# Measurements.net
KiCad netlist of a schematic drawn in Altium Designer
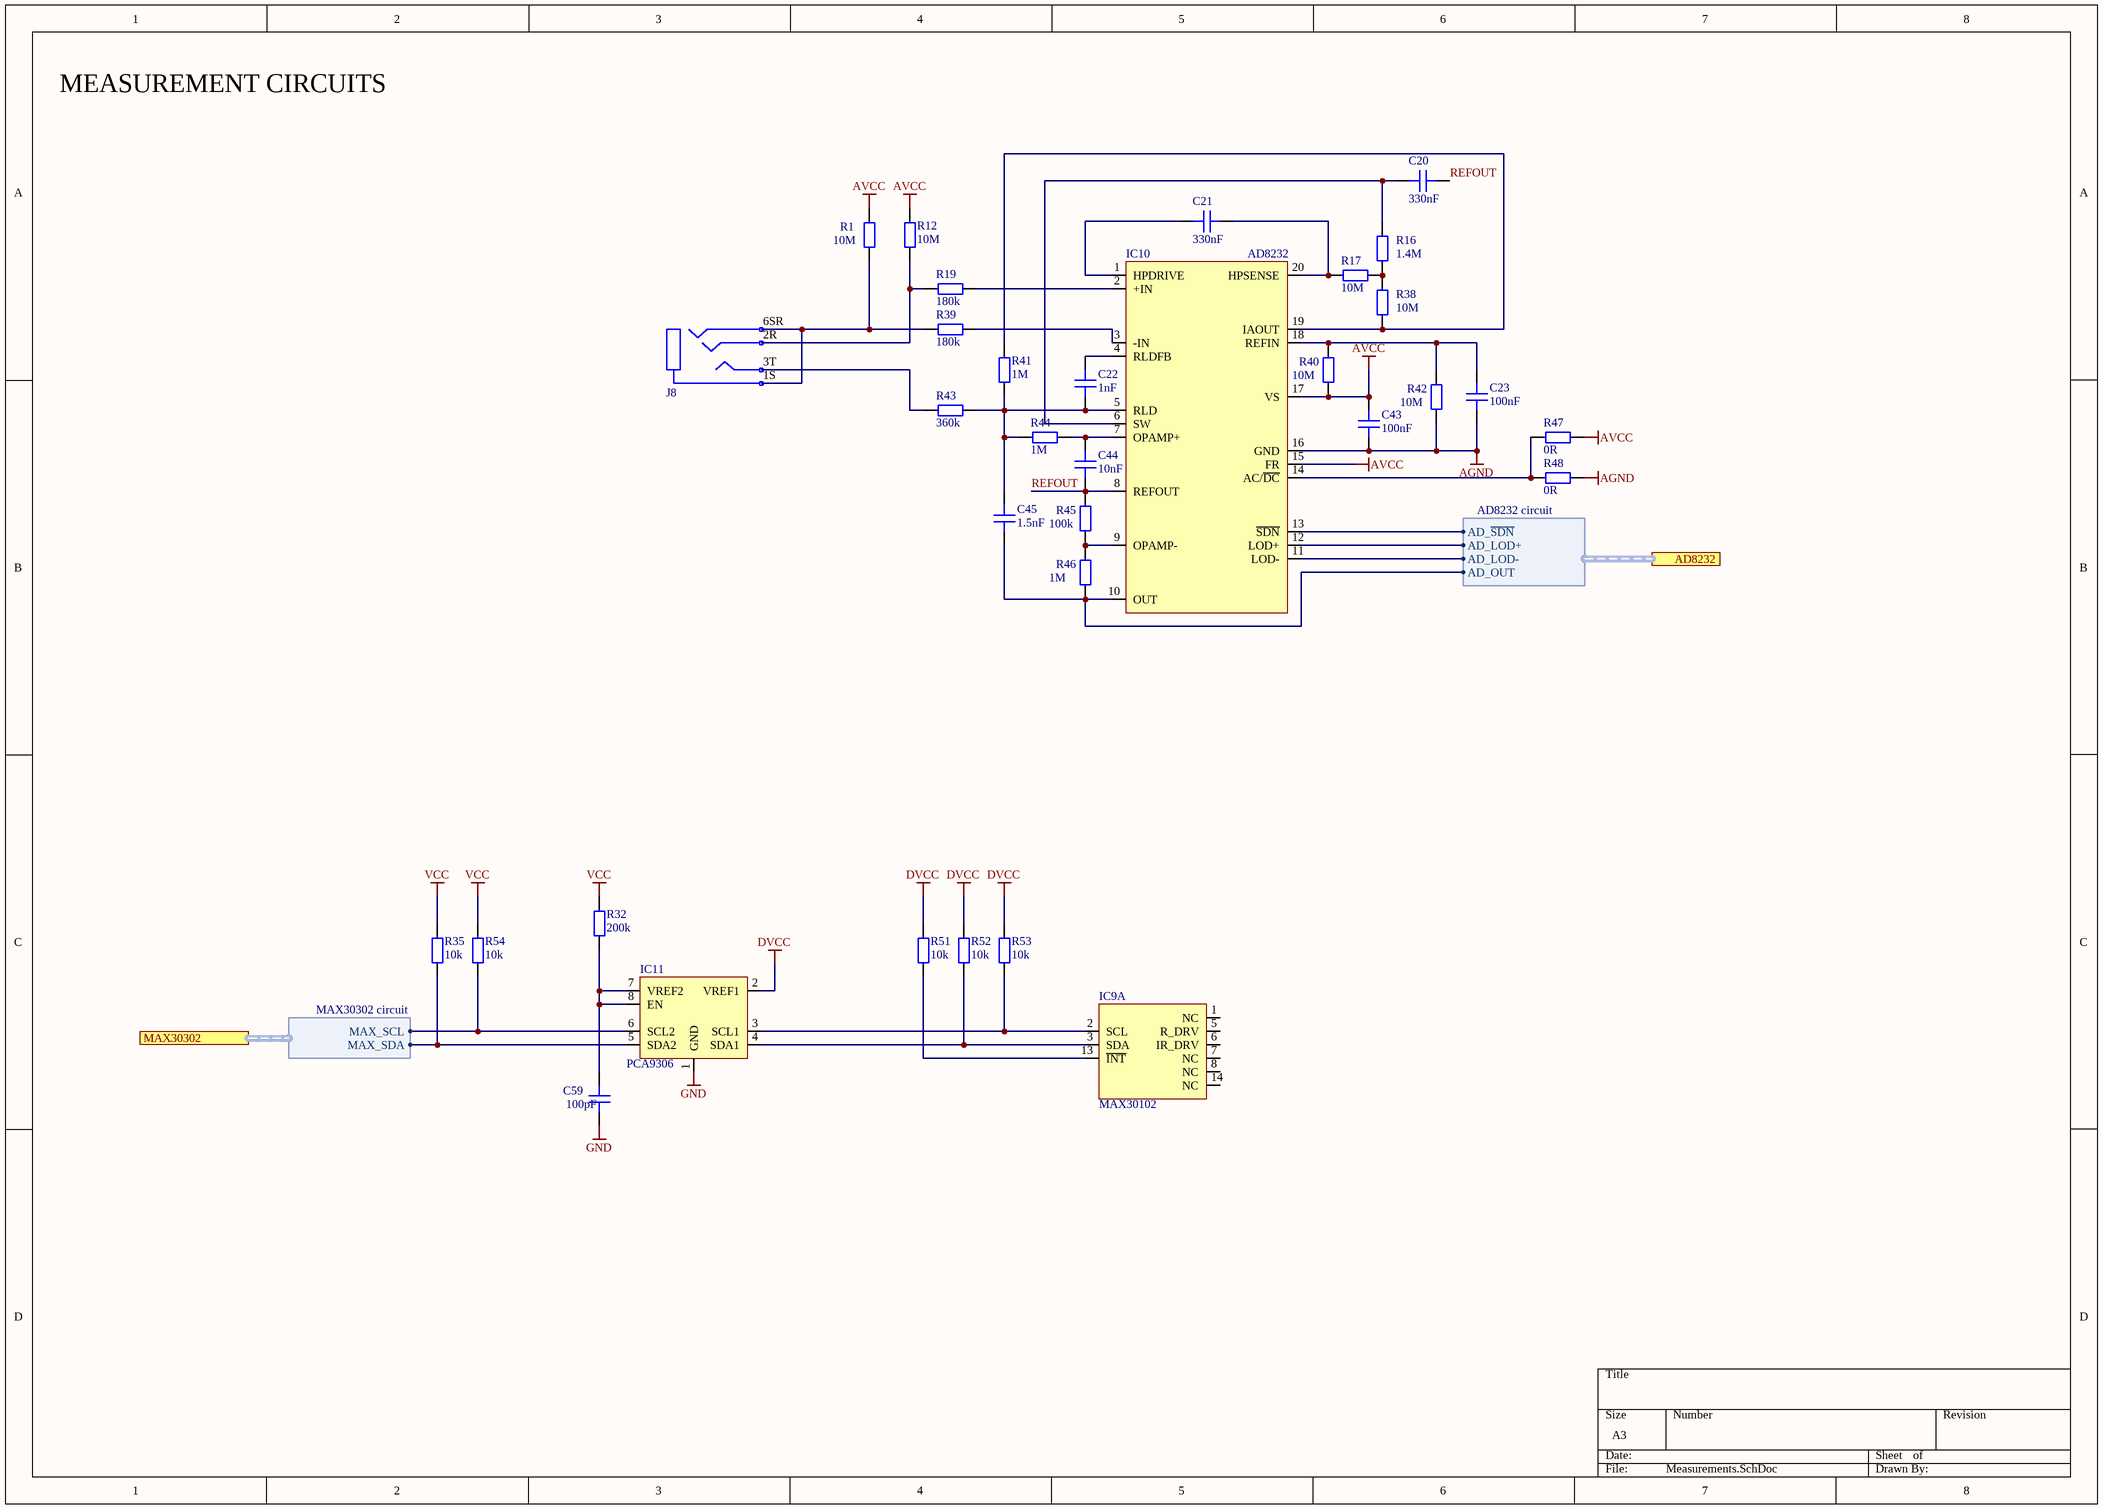
[diagram p0: Measurements.SchDoc]

(export (version "E")
  (design (tool "Eeschema 10.0.6"))
  (components
    (comp (ref "C20")
      (value "330nF")
      (footprint "CAP 0603")
      (description "SMT Capacitor")
      (libsource (lib "Passive") (part "Capacitor"))
    )
    (comp (ref "C21")
      (value "330nF")
      (footprint "CAP 0603")
      (description "SMT Capacitor")
      (libsource (lib "Passive") (part "Capacitor"))
    )
    (comp (ref "C22")
      (value "1nF")
      (footprint "CAP 0603")
      (description "SMT Capacitor")
      (libsource (lib "Passive") (part "Capacitor"))
    )
    (comp (ref "C23")
      (value "100nF")
      (footprint "CAP 0603")
      (description "SMT Capacitor")
      (libsource (lib "Passive") (part "Capacitor"))
    )
    (comp (ref "C43")
      (value "100nF")
      (footprint "CAP 0603")
      (description "SMT Capacitor")
      (libsource (lib "Passive") (part "Capacitor"))
    )
    (comp (ref "C44")
      (value "10nF")
      (footprint "CAP 0603")
      (description "SMT Capacitor")
      (libsource (lib "Passive") (part "Capacitor"))
    )
    (comp (ref "C45")
      (value "1.5nF")
      (footprint "CAP 0603")
      (description "SMT Capacitor")
      (libsource (lib "Passive") (part "Capacitor"))
    )
    (comp (ref "C59")
      (value "100pF")
      (footprint "CAP 0603")
      (description "SMT Capacitor")
      (libsource (lib "Passive") (part "Capacitor"))
    )
    (comp (ref "IC9")
      (value "MAX30102")
      (footprint "MAX30102")
      (description "Pulse Oximeter and Heart-Rate Sensor")
      (libsource (lib "IC") (part "MAX30102"))
    )
    (comp (ref "IC10")
      (value "AD8232")
      (footprint "LFCSP 20")
      (description "Single-Lead, Heart Rate Monitor Front End")
      (libsource (lib "IC") (part "AD8232"))
    )
    (comp (ref "IC11")
      (value "PCA9306")
      (footprint "SSOP8")
      (description "Dual Bidirectional I2C Bus and SMBus Voltage-Level Translator")
      (libsource (lib "IC") (part "PCA9306"))
    )
    (comp (ref "J8")
      (value "4 pin")
      (footprint "CLIFF FC68126")
      (description "Jack 3,5mm, dock, female")
      (libsource (lib "Connectors") (part "CLIFF FC68127 3.5mm"))
    )
    (comp (ref "R1")
      (value "10M")
      (footprint "RES 0603")
      (description "SMDResistor")
      (libsource (lib "Passive") (part "Resistor"))
    )
    (comp (ref "R12")
      (value "10M")
      (footprint "RES 0603")
      (description "SMDResistor")
      (libsource (lib "Passive") (part "Resistor"))
    )
    (comp (ref "R16")
      (value "1.4M")
      (footprint "RES 0603")
      (description "SMDResistor")
      (libsource (lib "Passive") (part "Resistor"))
    )
    (comp (ref "R17")
      (value "10M")
      (footprint "RES 0603")
      (description "SMDResistor")
      (libsource (lib "Passive") (part "Resistor"))
    )
    (comp (ref "R19")
      (value "180k")
      (footprint "RES 0603")
      (description "SMDResistor")
      (libsource (lib "Passive") (part "Resistor"))
    )
    (comp (ref "R32")
      (value "200k")
      (footprint "RES 0603")
      (description "SMDResistor")
      (libsource (lib "Passive") (part "Resistor"))
    )
    (comp (ref "R35")
      (value "10k")
      (footprint "RES 0603")
      (description "SMDResistor")
      (libsource (lib "Passive") (part "Resistor"))
    )
    (comp (ref "R38")
      (value "10M")
      (footprint "RES 0603")
      (description "SMDResistor")
      (libsource (lib "Passive") (part "Resistor"))
    )
    (comp (ref "R39")
      (value "180k")
      (footprint "RES 0603")
      (description "SMDResistor")
      (libsource (lib "Passive") (part "Resistor"))
    )
    (comp (ref "R40")
      (value "10M")
      (footprint "RES 0603")
      (description "SMDResistor")
      (libsource (lib "Passive") (part "Resistor"))
    )
    (comp (ref "R41")
      (value "1M")
      (footprint "RES 0603")
      (description "SMDResistor")
      (libsource (lib "Passive") (part "Resistor"))
    )
    (comp (ref "R42")
      (value "10M")
      (footprint "RES 0603")
      (description "SMDResistor")
      (libsource (lib "Passive") (part "Resistor"))
    )
    (comp (ref "R43")
      (value "360k")
      (footprint "RES 0603")
      (description "SMDResistor")
      (libsource (lib "Passive") (part "Resistor"))
    )
    (comp (ref "R44")
      (value "1M")
      (footprint "RES 0603")
      (description "SMDResistor")
      (libsource (lib "Passive") (part "Resistor"))
    )
    (comp (ref "R45")
      (value "100k")
      (footprint "RES 0603")
      (description "SMDResistor")
      (libsource (lib "Passive") (part "Resistor"))
    )
    (comp (ref "R46")
      (value "1M")
      (footprint "RES 0603")
      (description "SMDResistor")
      (libsource (lib "Passive") (part "Resistor"))
    )
    (comp (ref "R47")
      (value "0R")
      (footprint "RES 0603")
      (description "SMDResistor")
      (libsource (lib "Passive") (part "Resistor"))
    )
    (comp (ref "R48")
      (value "0R")
      (footprint "RES 0603")
      (description "SMDResistor")
      (libsource (lib "Passive") (part "Resistor"))
    )
    (comp (ref "R51")
      (value "10k")
      (footprint "RES 0603")
      (description "SMDResistor")
      (libsource (lib "Passive") (part "Resistor"))
    )
    (comp (ref "R52")
      (value "10k")
      (footprint "RES 0603")
      (description "SMDResistor")
      (libsource (lib "Passive") (part "Resistor"))
    )
    (comp (ref "R53")
      (value "10k")
      (footprint "RES 0603")
      (description "SMDResistor")
      (libsource (lib "Passive") (part "Resistor"))
    )
    (comp (ref "R54")
      (value "10k")
      (footprint "RES 0603")
      (description "SMDResistor")
      (libsource (lib "Passive") (part "Resistor"))
    )
  )
  (nets
    (net (code "4") (name "/AD_LOD+") (class "Default")
      (node (ref "IC10") (pin "12") (pinfunction "LOD+_12") (pintype "passive"))
    )
    (net (code "5") (name "/AD_LOD-") (class "Default")
      (node (ref "IC10") (pin "11") (pinfunction "LOD-_11") (pintype "passive"))
    )
    (net (code "6") (name "/AD_OUT") (class "Default")
      (node (ref "C45") (pin "1") (pinfunction "1_1") (pintype "passive"))
      (node (ref "IC10") (pin "10") (pinfunction "OUT_10") (pintype "passive"))
      (node (ref "R46") (pin "1") (pinfunction "1_1") (pintype "passive"))
    )
    (net (code "7") (name "/AD_~{SDN}") (class "Default")
      (node (ref "IC10") (pin "13") (pinfunction "~{SDN}_13") (pintype "passive"))
    )
    (net (code "8") (name "/MAX_SCL") (class "Default")
      (node (ref "IC11") (pin "6") (pinfunction "SCL2_6") (pintype "passive"))
      (node (ref "R54") (pin "1") (pinfunction "1_1") (pintype "passive"))
    )
    (net (code "9") (name "/MAX_SDA") (class "Default")
      (node (ref "IC11") (pin "5") (pinfunction "SDA2_5") (pintype "passive"))
      (node (ref "R35") (pin "1") (pinfunction "1_1") (pintype "passive"))
    )
    (net (code "10") (name "/REFOUT") (class "Default")
      (node (ref "C20") (pin "1") (pinfunction "1_1") (pintype "passive"))
      (node (ref "C44") (pin "1") (pinfunction "1_1") (pintype "passive"))
      (node (ref "IC10") (pin "8") (pinfunction "REFOUT_8") (pintype "passive"))
      (node (ref "R45") (pin "2") (pinfunction "2_2") (pintype "passive"))
    )
    (net (code "13") (name "AGND") (class "Default")
      (node (ref "C23") (pin "1") (pinfunction "1_1") (pintype "passive"))
      (node (ref "C43") (pin "1") (pinfunction "1_1") (pintype "passive"))
      (node (ref "IC10") (pin "16") (pinfunction "GND_16") (pintype "passive"))
      (node (ref "R42") (pin "1") (pinfunction "1_1") (pintype "passive"))
      (node (ref "R48") (pin "1") (pinfunction "1_1") (pintype "passive"))
    )
    (net (code "14") (name "AVCC") (class "Default")
      (node (ref "C43") (pin "2") (pinfunction "2_2") (pintype "passive"))
      (node (ref "IC10") (pin "15") (pinfunction "FR_15") (pintype "passive"))
      (node (ref "IC10") (pin "17") (pinfunction "VS_17") (pintype "passive"))
      (node (ref "R1") (pin "2") (pinfunction "2_2") (pintype "passive"))
      (node (ref "R12") (pin "1") (pinfunction "1_1") (pintype "passive"))
      (node (ref "R40") (pin "1") (pinfunction "1_1") (pintype "passive"))
      (node (ref "R47") (pin "2") (pinfunction "2_2") (pintype "passive"))
    )
    (net (code "15") (name "DVCC") (class "Default")
      (node (ref "IC11") (pin "2") (pinfunction "VREF1_2") (pintype "passive"))
      (node (ref "R51") (pin "2") (pinfunction "2_2") (pintype "passive"))
      (node (ref "R52") (pin "2") (pinfunction "2_2") (pintype "passive"))
      (node (ref "R53") (pin "2") (pinfunction "2_2") (pintype "passive"))
    )
    (net (code "16") (name "GND") (class "Default")
      (node (ref "C59") (pin "1") (pinfunction "1_1") (pintype "passive"))
      (node (ref "IC11") (pin "1") (pinfunction "GND_1") (pintype "passive"))
    )
    (net (code "17") (name "Net-(IC9A-~{INT})") (class "Default")
      (node (ref "IC9") (pin "13") (pinfunction "~{INT}_13") (pintype "passive"))
      (node (ref "R51") (pin "1") (pinfunction "1_1") (pintype "passive"))
    )
    (net (code "18") (name "Net-(IC10-+IN)") (class "Default")
      (node (ref "IC10") (pin "2") (pinfunction "+IN_2") (pintype "passive"))
      (node (ref "R19") (pin "1") (pinfunction "1_1") (pintype "passive"))
    )
    (net (code "19") (name "Net-(IC10--IN)") (class "Default")
      (node (ref "IC10") (pin "3") (pinfunction "-IN_3") (pintype "passive"))
      (node (ref "R39") (pin "1") (pinfunction "1_1") (pintype "passive"))
    )
    (net (code "20") (name "Net-(IC10-AC{slash}~{DC})") (class "Default")
      (node (ref "IC10") (pin "14") (pinfunction "AC/~{DC}_14") (pintype "passive"))
      (node (ref "R47") (pin "1") (pinfunction "1_1") (pintype "passive"))
      (node (ref "R48") (pin "2") (pinfunction "2_2") (pintype "passive"))
    )
    (net (code "21") (name "Net-(IC10-HPDRIVE)") (class "Default")
      (node (ref "C21") (pin "2") (pinfunction "2_2") (pintype "passive"))
      (node (ref "IC10") (pin "1") (pinfunction "HPDRIVE_1") (pintype "passive"))
    )
    (net (code "22") (name "Net-(IC10-HPSENSE)") (class "Default")
      (node (ref "C21") (pin "1") (pinfunction "1_1") (pintype "passive"))
      (node (ref "IC10") (pin "20") (pinfunction "HPSENSE_20") (pintype "passive"))
      (node (ref "R17") (pin "2") (pinfunction "2_2") (pintype "passive"))
    )
    (net (code "23") (name "Net-(IC10-IAOUT)") (class "Default")
      (node (ref "IC10") (pin "19") (pinfunction "IAOUT_19") (pintype "passive"))
      (node (ref "R38") (pin "1") (pinfunction "1_1") (pintype "passive"))
      (node (ref "R41") (pin "1") (pinfunction "1_1") (pintype "passive"))
    )
    (net (code "24") (name "Net-(IC10-OPAMP+)") (class "Default")
      (node (ref "C44") (pin "2") (pinfunction "2_2") (pintype "passive"))
      (node (ref "IC10") (pin "7") (pinfunction "OPAMP+_7") (pintype "passive"))
      (node (ref "R44") (pin "1") (pinfunction "1_1") (pintype "passive"))
    )
    (net (code "25") (name "Net-(IC10-OPAMP-)") (class "Default")
      (node (ref "IC10") (pin "9") (pinfunction "OPAMP-_9") (pintype "passive"))
      (node (ref "R45") (pin "1") (pinfunction "1_1") (pintype "passive"))
      (node (ref "R46") (pin "2") (pinfunction "2_2") (pintype "passive"))
    )
    (net (code "26") (name "Net-(IC10-REFIN)") (class "Default")
      (node (ref "C23") (pin "2") (pinfunction "2_2") (pintype "passive"))
      (node (ref "IC10") (pin "18") (pinfunction "REFIN_18") (pintype "passive"))
      (node (ref "R40") (pin "2") (pinfunction "2_2") (pintype "passive"))
      (node (ref "R42") (pin "2") (pinfunction "2_2") (pintype "passive"))
    )
    (net (code "27") (name "Net-(IC10-RLD)") (class "Default")
      (node (ref "C22") (pin "1") (pinfunction "1_1") (pintype "passive"))
      (node (ref "C45") (pin "2") (pinfunction "2_2") (pintype "passive"))
      (node (ref "IC10") (pin "5") (pinfunction "RLD_5") (pintype "passive"))
      (node (ref "R41") (pin "2") (pinfunction "2_2") (pintype "passive"))
      (node (ref "R43") (pin "1") (pinfunction "1_1") (pintype "passive"))
      (node (ref "R44") (pin "2") (pinfunction "2_2") (pintype "passive"))
    )
    (net (code "28") (name "Net-(IC10-RLDFB)") (class "Default")
      (node (ref "C22") (pin "2") (pinfunction "2_2") (pintype "passive"))
      (node (ref "IC10") (pin "4") (pinfunction "RLDFB_4") (pintype "passive"))
    )
    (net (code "29") (name "Net-(IC10-SW)") (class "Default")
      (node (ref "C20") (pin "2") (pinfunction "2_2") (pintype "passive"))
      (node (ref "IC10") (pin "6") (pinfunction "SW_6") (pintype "passive"))
      (node (ref "R16") (pin "2") (pinfunction "2_2") (pintype "passive"))
    )
    (net (code "30") (name "Net-(IC11-EN)") (class "Default")
      (node (ref "C59") (pin "2") (pinfunction "2_2") (pintype "passive"))
      (node (ref "IC11") (pin "7") (pinfunction "VREF2_7") (pintype "passive"))
      (node (ref "IC11") (pin "8") (pinfunction "EN_8") (pintype "passive"))
      (node (ref "R32") (pin "1") (pinfunction "1_1") (pintype "passive"))
    )
    (net (code "31") (name "Net-(IC11-SCL1)") (class "Default")
      (node (ref "IC11") (pin "3") (pinfunction "SCL1_3") (pintype "passive"))
      (node (ref "IC9") (pin "2") (pinfunction "SCL_2") (pintype "passive"))
      (node (ref "R53") (pin "1") (pinfunction "1_1") (pintype "passive"))
    )
    (net (code "32") (name "Net-(IC11-SDA1)") (class "Default")
      (node (ref "IC11") (pin "4") (pinfunction "SDA1_4") (pintype "passive"))
      (node (ref "IC9") (pin "3") (pinfunction "SDA_3") (pintype "passive"))
      (node (ref "R52") (pin "1") (pinfunction "1_1") (pintype "passive"))
    )
    (net (code "33") (name "Net-(J8-1)") (class "Default")
      (node (ref "J8") (pin "1S") (pinfunction "1_1S") (pintype "passive"))
      (node (ref "J8") (pin "6SR") (pinfunction "6_6SR") (pintype "passive"))
      (node (ref "R1") (pin "1") (pinfunction "1_1") (pintype "passive"))
      (node (ref "R39") (pin "2") (pinfunction "2_2") (pintype "passive"))
    )
    (net (code "34") (name "Net-(J8-2)") (class "Default")
      (node (ref "J8") (pin "2R") (pinfunction "2_2R") (pintype "passive"))
      (node (ref "R12") (pin "2") (pinfunction "2_2") (pintype "passive"))
      (node (ref "R19") (pin "2") (pinfunction "2_2") (pintype "passive"))
    )
    (net (code "35") (name "Net-(J8-3)") (class "Default")
      (node (ref "J8") (pin "3T") (pinfunction "3_3T") (pintype "passive"))
      (node (ref "R43") (pin "2") (pinfunction "2_2") (pintype "passive"))
    )
    (net (code "36") (name "Net-(R16-Pad1)") (class "Default")
      (node (ref "R16") (pin "1") (pinfunction "1_1") (pintype "passive"))
      (node (ref "R17") (pin "1") (pinfunction "1_1") (pintype "passive"))
      (node (ref "R38") (pin "2") (pinfunction "2_2") (pintype "passive"))
    )
    (net (code "37") (name "VCC") (class "Default")
      (node (ref "R32") (pin "2") (pinfunction "2_2") (pintype "passive"))
      (node (ref "R35") (pin "2") (pinfunction "2_2") (pintype "passive"))
      (node (ref "R54") (pin "2") (pinfunction "2_2") (pintype "passive"))
    )
    (net (code "38") (name "unconnected-(IC9A-IR_DRV-Pad6)") (class "Default")
      (node (ref "IC9") (pin "6") (pinfunction "IR_DRV_6") (pintype "passive"))
    )
    (net (code "39") (name "unconnected-(IC9A-NC-Pad1)") (class "Default")
      (node (ref "IC9") (pin "1") (pinfunction "NC_1") (pintype "passive"))
    )
    (net (code "40") (name "unconnected-(IC9A-NC-Pad7)") (class "Default")
      (node (ref "IC9") (pin "7") (pinfunction "NC_7") (pintype "passive"))
    )
    (net (code "41") (name "unconnected-(IC9A-NC-Pad8)") (class "Default")
      (node (ref "IC9") (pin "8") (pinfunction "NC_8") (pintype "passive"))
    )
    (net (code "42") (name "unconnected-(IC9A-NC-Pad14)") (class "Default")
      (node (ref "IC9") (pin "14") (pinfunction "NC_14") (pintype "passive"))
    )
    (net (code "43") (name "unconnected-(IC9A-R_DRV-Pad5)") (class "Default")
      (node (ref "IC9") (pin "5") (pinfunction "R_DRV_5") (pintype "passive"))
    )
  )
)
